# Sheet1.net
KiCad netlist of a schematic drawn in Altium Designer
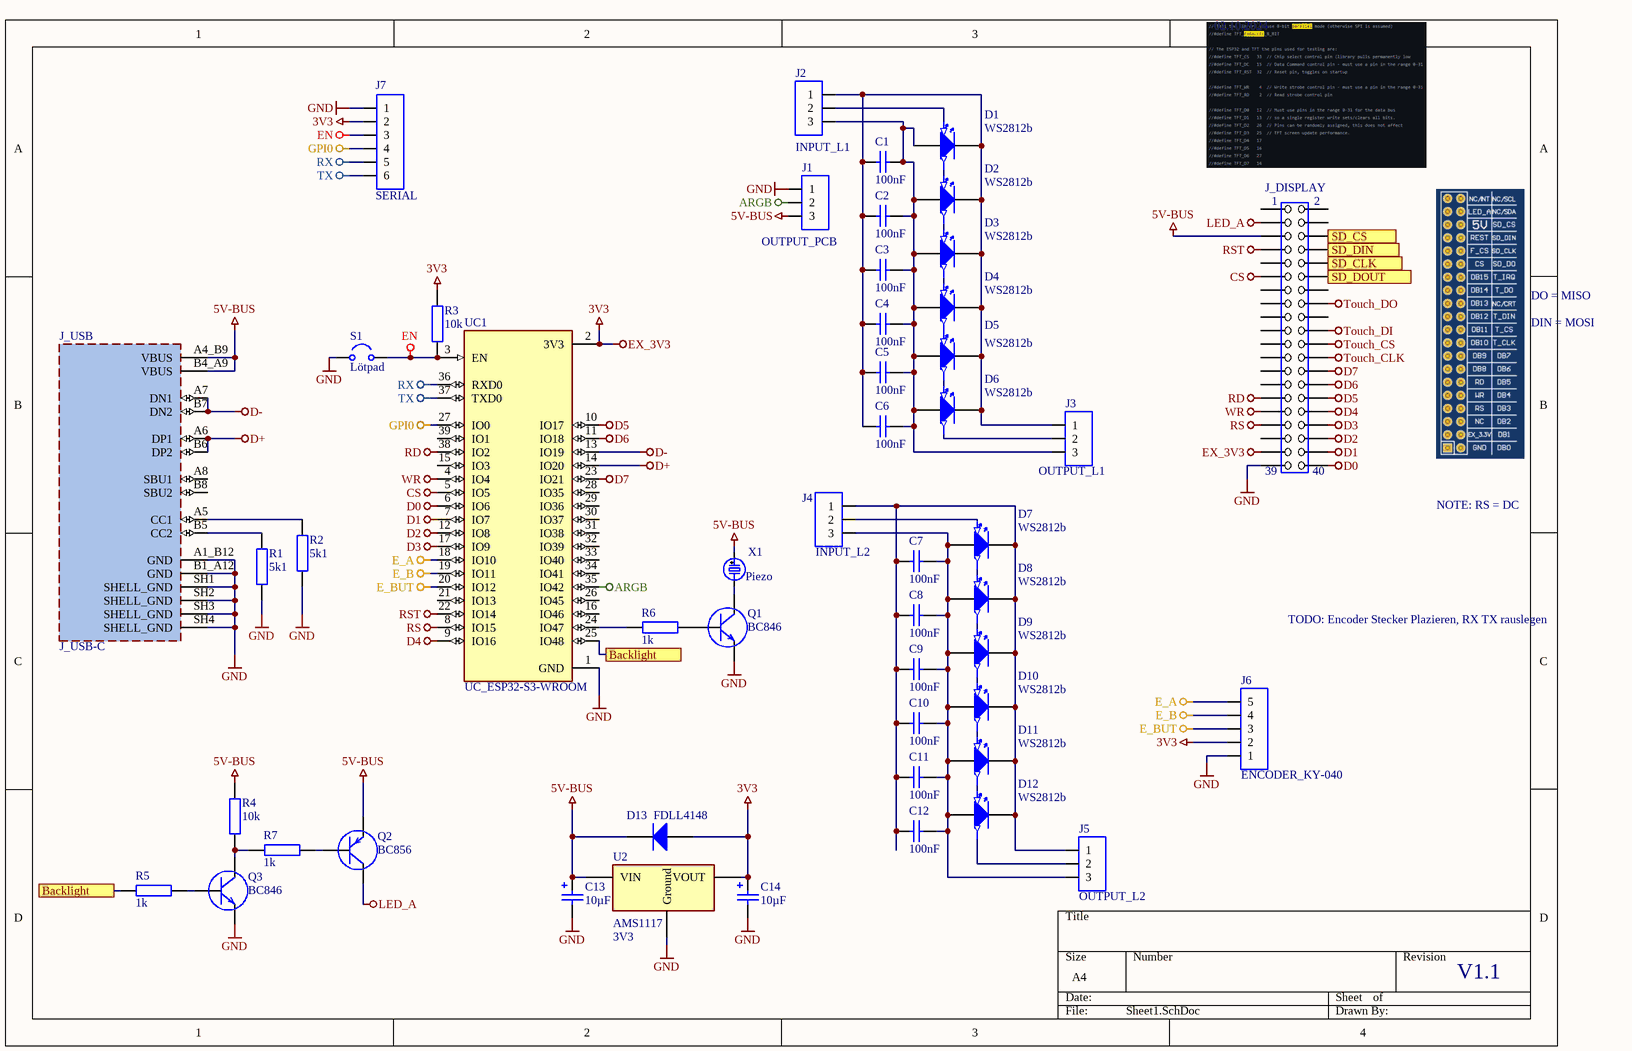
[diagram p0: Sheet1.SchDoc]

(export (version "E")
  (design (tool "Eeschema 10.0.6"))
  (components
    (comp (ref "C1")
      (value "100nF")
      (footprint "C_SMD_0603")
      (description "Kondensator SMD Universal, Keramik, Folie, usw.")
      (libsource (lib "SCHLIB-PCSB_5.1.3") (part "C_SMD_KO"))
    )
    (comp (ref "C2")
      (value "100nF")
      (footprint "C_SMD_0603")
      (description "Kondensator SMD Universal, Keramik, Folie, usw.")
      (libsource (lib "SCHLIB-PCSB_5.1.3") (part "C_SMD_KO"))
    )
    (comp (ref "C3")
      (value "100nF")
      (footprint "C_SMD_0603")
      (description "Kondensator SMD Universal, Keramik, Folie, usw.")
      (libsource (lib "SCHLIB-PCSB_5.1.3") (part "C_SMD_KO"))
    )
    (comp (ref "C4")
      (value "100nF")
      (footprint "C_SMD_0603")
      (description "Kondensator SMD Universal, Keramik, Folie, usw.")
      (libsource (lib "SCHLIB-PCSB_5.1.3") (part "C_SMD_KO"))
    )
    (comp (ref "C5")
      (value "100nF")
      (footprint "C_SMD_0603")
      (description "Kondensator SMD Universal, Keramik, Folie, usw.")
      (libsource (lib "SCHLIB-PCSB_5.1.3") (part "C_SMD_KO"))
    )
    (comp (ref "C6")
      (value "100nF")
      (footprint "C_SMD_0603")
      (description "Kondensator SMD Universal, Keramik, Folie, usw.")
      (libsource (lib "SCHLIB-PCSB_5.1.3") (part "C_SMD_KO"))
    )
    (comp (ref "C7")
      (value "100nF")
      (footprint "C_SMD_0603")
      (description "Kondensator SMD Universal, Keramik, Folie, usw.")
      (libsource (lib "SCHLIB-PCSB_5.1.3") (part "C_SMD_KO"))
    )
    (comp (ref "C8")
      (value "100nF")
      (footprint "C_SMD_0603")
      (description "Kondensator SMD Universal, Keramik, Folie, usw.")
      (libsource (lib "SCHLIB-PCSB_5.1.3") (part "C_SMD_KO"))
    )
    (comp (ref "C9")
      (value "100nF")
      (footprint "C_SMD_0603")
      (description "Kondensator SMD Universal, Keramik, Folie, usw.")
      (libsource (lib "SCHLIB-PCSB_5.1.3") (part "C_SMD_KO"))
    )
    (comp (ref "C10")
      (value "100nF")
      (footprint "C_SMD_0603")
      (description "Kondensator SMD Universal, Keramik, Folie, usw.")
      (libsource (lib "SCHLIB-PCSB_5.1.3") (part "C_SMD_KO"))
    )
    (comp (ref "C11")
      (value "100nF")
      (footprint "C_SMD_0603")
      (description "Kondensator SMD Universal, Keramik, Folie, usw.")
      (libsource (lib "SCHLIB-PCSB_5.1.3") (part "C_SMD_KO"))
    )
    (comp (ref "C12")
      (value "100nF")
      (footprint "C_SMD_0603")
      (description "Kondensator SMD Universal, Keramik, Folie, usw.")
      (libsource (lib "SCHLIB-PCSB_5.1.3") (part "C_SMD_KO"))
    )
    (comp (ref "C13")
      (value "10µF")
      (footprint "C_SMD_B-Typ")
      (description "SMD Elektrolytkondensator")
      (libsource (lib "SCHLIB-PCSB_5.1.3") (part "C_SMD_ELK"))
    )
    (comp (ref "C14")
      (value "10µF")
      (footprint "C_SMD_B-Typ")
      (description "SMD Elektrolytkondensator")
      (libsource (lib "SCHLIB-PCSB_5.1.3") (part "C_SMD_ELK"))
    )
    (comp (ref "D1")
      (value "WS2812b")
      (footprint "D_SMD_LED-ARGB")
      (description "Diode SMD ARGB")
      (libsource (lib "SCHLIB-PCSB_5.1.3") (part "D_SMD_LED-ARGB"))
    )
    (comp (ref "D2")
      (value "WS2812b")
      (footprint "D_SMD_LED-ARGB")
      (description "Diode SMD ARGB")
      (libsource (lib "SCHLIB-PCSB_5.1.3") (part "D_SMD_LED-ARGB"))
    )
    (comp (ref "D3")
      (value "WS2812b")
      (footprint "D_SMD_LED-ARGB")
      (description "Diode SMD ARGB")
      (libsource (lib "SCHLIB-PCSB_5.1.3") (part "D_SMD_LED-ARGB"))
    )
    (comp (ref "D4")
      (value "WS2812b")
      (footprint "D_SMD_LED-ARGB")
      (description "Diode SMD ARGB")
      (libsource (lib "SCHLIB-PCSB_5.1.3") (part "D_SMD_LED-ARGB"))
    )
    (comp (ref "D5")
      (value "WS2812b")
      (footprint "D_SMD_LED-ARGB")
      (description "Diode SMD ARGB")
      (libsource (lib "SCHLIB-PCSB_5.1.3") (part "D_SMD_LED-ARGB"))
    )
    (comp (ref "D6")
      (value "WS2812b")
      (footprint "D_SMD_LED-ARGB")
      (description "Diode SMD ARGB")
      (libsource (lib "SCHLIB-PCSB_5.1.3") (part "D_SMD_LED-ARGB"))
    )
    (comp (ref "D7")
      (value "WS2812b")
      (footprint "D_SMD_LED-ARGB")
      (description "Diode SMD ARGB")
      (libsource (lib "SCHLIB-PCSB_5.1.3") (part "D_SMD_LED-ARGB"))
    )
    (comp (ref "D8")
      (value "WS2812b")
      (footprint "D_SMD_LED-ARGB")
      (description "Diode SMD ARGB")
      (libsource (lib "SCHLIB-PCSB_5.1.3") (part "D_SMD_LED-ARGB"))
    )
    (comp (ref "D9")
      (value "WS2812b")
      (footprint "D_SMD_LED-ARGB")
      (description "Diode SMD ARGB")
      (libsource (lib "SCHLIB-PCSB_5.1.3") (part "D_SMD_LED-ARGB"))
    )
    (comp (ref "D10")
      (value "WS2812b")
      (footprint "D_SMD_LED-ARGB")
      (description "Diode SMD ARGB")
      (libsource (lib "SCHLIB-PCSB_5.1.3") (part "D_SMD_LED-ARGB"))
    )
    (comp (ref "D11")
      (value "WS2812b")
      (footprint "D_SMD_LED-ARGB")
      (description "Diode SMD ARGB")
      (libsource (lib "SCHLIB-PCSB_5.1.3") (part "D_SMD_LED-ARGB"))
    )
    (comp (ref "D12")
      (value "WS2812b")
      (footprint "D_SMD_LED-ARGB")
      (description "Diode SMD ARGB")
      (libsource (lib "SCHLIB-PCSB_5.1.3") (part "D_SMD_LED-ARGB"))
    )
    (comp (ref "D13")
      (value "FDLL4148")
      (footprint "SOD-80-2")
      (description "Diode SMD Silizium")
      (libsource (lib "SCHLIB-PCSB_5.1.3") (part "D_SMD_Silizium"))
    )
    (comp (ref "J1")
      (value "OUTPUT_PCB")
      (footprint "Sip-3")
      (description "Stecker")
      (libsource (lib "SCHLIB-PCSB_5.1.3") (part "J_THT_CON3"))
    )
    (comp (ref "J2")
      (value "INPUT_L1")
      (footprint "Sip-3")
      (description "Stecker")
      (libsource (lib "") (part "J_THT_CON3_1"))
    )
    (comp (ref "J3")
      (value "OUTPUT_L1")
      (footprint "Sip-3")
      (description "Stecker")
      (libsource (lib "SCHLIB-PCSB_5.1.3") (part "J_THT_CON3"))
    )
    (comp (ref "J4")
      (value "INPUT_L2")
      (footprint "Sip-3")
      (description "Stecker")
      (libsource (lib "") (part "J_THT_CON3_1"))
    )
    (comp (ref "J5")
      (value "OUTPUT_L2")
      (footprint "Sip-3")
      (description "Stecker")
      (libsource (lib "SCHLIB-PCSB_5.1.3") (part "J_THT_CON3"))
    )
    (comp (ref "J6")
      (value "ENCODER_KY-040")
      (footprint "SIP-5")
      (description "Stecker")
      (libsource (lib "SCHLIB-PCSB_5.1.3") (part "J_THT_CON5"))
    )
    (comp (ref "J7")
      (value "SERIAL")
      (footprint "SIP-6")
      (description "Stecker")
      (libsource (lib "SCHLIB-PCSB_5.1.3") (part "J_THT_CON6"))
    )
    (comp (ref "J_DISPLAY")
      (value "DISPLAY")
      (footprint "J_2x20")
      (description "IDC-Con 2x20")
      (libsource (lib "SCHLIB-PCSB_5.1.3") (part "J_THT_IDC 2x20"))
    )
    (comp (ref "J_USB")
      (value "J_USB-C")
      (footprint "GCT_USB4105-GF-A")
      (description "USB4105-GF-")
      (fields (field (name "MF") "{'manufacturer': u'GCT'}") (field (name "MP") "USB4105-GF-A"))
      (libsource (lib "SCHLIB-PCSB_5.1.3") (part "J_USB-C"))
    )
    (comp (ref "Q1")
      (value "BC846")
      (footprint "SOT-23-3_BC846")
      (description "NPN Transistor")
      (libsource (lib "SCHLIB-PCSB_5.1.3") (part "Q_SMD_NPN"))
    )
    (comp (ref "Q2")
      (value "BC856")
      (footprint "SOT-23-3_BC856")
      (description "PNP Transistor")
      (libsource (lib "SCHLIB-PCSB_5.1.3") (part "Q_SMD_PNP"))
    )
    (comp (ref "Q3")
      (value "BC846")
      (footprint "SOT-23-3_BC846")
      (description "NPN Transistor")
      (libsource (lib "SCHLIB-PCSB_5.1.3") (part "Q_SMD_NPN"))
    )
    (comp (ref "R1")
      (value "5k1")
      (footprint "R_SMD_0805")
      (description "Widerstand SMD")
      (libsource (lib "SCHLIB-PCSB_5.1.3") (part "R_SMD_Widerstand"))
    )
    (comp (ref "R2")
      (value "5k1")
      (footprint "R_SMD_0805")
      (description "Widerstand SMD")
      (libsource (lib "SCHLIB-PCSB_5.1.3") (part "R_SMD_Widerstand"))
    )
    (comp (ref "R3")
      (value "10k")
      (footprint "R_SMD_0805")
      (description "Widerstand SMD")
      (libsource (lib "SCHLIB-PCSB_5.1.3") (part "R_SMD_Widerstand"))
    )
    (comp (ref "R4")
      (value "10k")
      (footprint "R_SMD_0805")
      (description "Widerstand SMD")
      (libsource (lib "SCHLIB-PCSB_5.1.3") (part "R_SMD_Widerstand"))
    )
    (comp (ref "R5")
      (value "1k")
      (footprint "R_SMD_0805")
      (description "Widerstand SMD")
      (libsource (lib "SCHLIB-PCSB_5.1.3") (part "R_SMD_Widerstand"))
    )
    (comp (ref "R6")
      (value "1k")
      (footprint "R_SMD_0805")
      (description "Widerstand SMD")
      (libsource (lib "SCHLIB-PCSB_5.1.3") (part "R_SMD_Widerstand"))
    )
    (comp (ref "R7")
      (value "1k")
      (footprint "R_SMD_0805")
      (description "Widerstand SMD")
      (libsource (lib "SCHLIB-PCSB_5.1.3") (part "R_SMD_Widerstand"))
    )
    (comp (ref "S1")
      (value "Lötpad")
      (footprint "S_SMD_Pad-NC")
      (description "Lötverbinder")
      (libsource (lib "SCHLIB-PCSB_5.1.3") (part "S_SMD_Jumper"))
    )
    (comp (ref "U2")
      (value "AMS1117")
      (footprint "U_SMD_AMS1117")
      (description "Linearwandler")
      (fields
        (field (name "MANUFACTURER PART NUMBER") "AMS1117-3.3")
        (field (name "OCTOPART") "https://octopart.com/ams1117-3.3-advanced+monolithic+systems-25899300")
      )
      (libsource (lib "SCHLIB-PCSB_5.1.3") (part "U_SMD_AMS1117"))
    )
    (comp (ref "UC1")
      (value "UC_ESP32-S3-WROOM")
      (footprint "XCVR_ESP32S3WROOM1N8R8")
      (description "Bluetooth, WiFi 802.11b/g/n, Bluetooth v5.0 Transceiver Module 2.4GHz PCB Trace Surface Mount")
      (fields (field (name "MF") "Espressif Systems") (field (name "MP") "ESP32-S3-WROOM-1-N8R8"))
      (libsource (lib "SCHLIB-PCSB_5.1.3") (part "UC_ESP32-S3-WROOM"))
    )
    (comp (ref "X1")
      (value "Piezo")
      (footprint "X_THT_PIEZZO")
      (description "Piezobuzzer")
      (libsource (lib "SCHLIB-PCSB_5.1.3") (part "X_THT_Piezo"))
    )
  )
  (nets
    (net (code "1") (name "/Backlight") (class "Default")
      (node (ref "R5") (pin "2") (pintype "passive"))
      (node (ref "UC1") (pin "25") (pinfunction "IO48_25") (pintype "bidirectional"))
    )
    (net (code "2") (name "/SD_CLK") (class "Default")
      (node (ref "J_DISPLAY") (pin "10") (pintype "passive"))
    )
    (net (code "3") (name "/SD_CS") (class "Default") (node (ref "J_DISPLAY") (pin "6") (pintype "passive")))
    (net (code "4") (name "/SD_DIN") (class "Default") (node (ref "J_DISPLAY") (pin "8") (pintype "passive")))
    (net (code "5") (name "/SD_DOUT") (class "Default")
      (node (ref "J_DISPLAY") (pin "12") (pintype "passive"))
    )
    (net (code "6") (name "3V3") (class "Default")
      (node (ref "C14") (pin "1") (pinfunction "1_1") (pintype "passive"))
      (node (ref "D13") (pin "1") (pinfunction "A_1") (pintype "passive"))
      (node (ref "J6") (pin "2") (pinfunction "2_2") (pintype "passive"))
      (node (ref "J7") (pin "2") (pinfunction "2_2") (pintype "passive"))
      (node (ref "J_DISPLAY") (pin "37") (pintype "passive"))
      (node (ref "R3") (pin "2") (pintype "passive"))
      (node (ref "U2") (pin "2") (pinfunction "VOUT_2") (pintype "passive"))
      (node (ref "UC1") (pin "2") (pinfunction "3V3_2") (pintype "power_in"))
    )
    (net (code "7") (name "5V-BUS") (class "Default")
      (node (ref "C13") (pin "1") (pinfunction "1_1") (pintype "passive"))
      (node (ref "D13") (pin "2") (pinfunction "K_2") (pintype "passive"))
      (node (ref "J1") (pin "3") (pinfunction "3_3") (pintype "passive"))
      (node (ref "J_DISPLAY") (pin "5") (pintype "passive"))
      (node (ref "J_USB") (pin "A4_B9") (pinfunction "VBUS_A4_B9") (pintype "power_in"))
      (node (ref "J_USB") (pin "B4_A9") (pinfunction "VBUS_B4_A9") (pintype "power_in"))
      (node (ref "Q2") (pin "E") (pinfunction "E_E") (pintype "passive"))
      (node (ref "R4") (pin "2") (pintype "passive"))
      (node (ref "U2") (pin "3") (pinfunction "VIN_3") (pintype "power_in"))
      (node (ref "X1") (pin "1") (pinfunction "1_1") (pintype "passive"))
    )
    (net (code "8") (name "ARGB") (class "Default")
      (node (ref "J1") (pin "2") (pinfunction "2_2") (pintype "passive"))
      (node (ref "UC1") (pin "35") (pinfunction "IO42_35") (pintype "bidirectional"))
    )
    (net (code "9") (name "CS") (class "Default")
      (node (ref "J_DISPLAY") (pin "11") (pintype "passive"))
      (node (ref "UC1") (pin "5") (pinfunction "IO5_5") (pintype "bidirectional"))
    )
    (net (code "10") (name "D+") (class "Default")
      (node (ref "J_USB") (pin "A6") (pinfunction "DP1_A6") (pintype "bidirectional"))
      (node (ref "J_USB") (pin "B6") (pinfunction "DP2_B6") (pintype "bidirectional"))
      (node (ref "UC1") (pin "14") (pinfunction "IO20_14") (pintype "bidirectional"))
    )
    (net (code "11") (name "D-") (class "Default")
      (node (ref "J_USB") (pin "A7") (pinfunction "DN1_A7") (pintype "bidirectional"))
      (node (ref "J_USB") (pin "B7") (pinfunction "DN2_B7") (pintype "bidirectional"))
      (node (ref "UC1") (pin "13") (pinfunction "IO19_13") (pintype "bidirectional"))
    )
    (net (code "12") (name "D0") (class "Default")
      (node (ref "J_DISPLAY") (pin "40") (pintype "passive"))
      (node (ref "UC1") (pin "6") (pinfunction "IO6_6") (pintype "bidirectional"))
    )
    (net (code "13") (name "D1") (class "Default")
      (node (ref "J_DISPLAY") (pin "38") (pintype "passive"))
      (node (ref "UC1") (pin "7") (pinfunction "IO7_7") (pintype "bidirectional"))
    )
    (net (code "14") (name "D2") (class "Default")
      (node (ref "J_DISPLAY") (pin "36") (pintype "passive"))
      (node (ref "UC1") (pin "12") (pinfunction "IO8_12") (pintype "bidirectional"))
    )
    (net (code "15") (name "D3") (class "Default")
      (node (ref "J_DISPLAY") (pin "34") (pintype "passive"))
      (node (ref "UC1") (pin "17") (pinfunction "IO9_17") (pintype "bidirectional"))
    )
    (net (code "16") (name "D4") (class "Default")
      (node (ref "J_DISPLAY") (pin "32") (pintype "passive"))
      (node (ref "UC1") (pin "9") (pinfunction "IO16_9") (pintype "bidirectional"))
    )
    (net (code "17") (name "D5") (class "Default")
      (node (ref "J_DISPLAY") (pin "30") (pintype "passive"))
      (node (ref "UC1") (pin "10") (pinfunction "IO17_10") (pintype "bidirectional"))
    )
    (net (code "18") (name "D6") (class "Default")
      (node (ref "J_DISPLAY") (pin "28") (pintype "passive"))
      (node (ref "UC1") (pin "11") (pinfunction "IO18_11") (pintype "bidirectional"))
    )
    (net (code "19") (name "D7") (class "Default")
      (node (ref "J_DISPLAY") (pin "26") (pintype "passive"))
      (node (ref "UC1") (pin "23") (pinfunction "IO21_23") (pintype "bidirectional"))
    )
    (net (code "20") (name "EN") (class "Default")
      (node (ref "J7") (pin "3") (pinfunction "3_3") (pintype "passive"))
      (node (ref "R3") (pin "1") (pintype "passive"))
      (node (ref "S1") (pin "2") (pinfunction "1_2") (pintype "passive"))
      (node (ref "UC1") (pin "3") (pinfunction "EN_3") (pintype "input"))
    )
    (net (code "21") (name "E_A") (class "Default")
      (node (ref "J6") (pin "5") (pinfunction "5_5") (pintype "passive"))
      (node (ref "UC1") (pin "18") (pinfunction "IO10_18") (pintype "bidirectional"))
    )
    (net (code "22") (name "E_B") (class "Default")
      (node (ref "J6") (pin "4") (pinfunction "4_4") (pintype "passive"))
      (node (ref "UC1") (pin "19") (pinfunction "IO11_19") (pintype "bidirectional"))
    )
    (net (code "23") (name "E_BUT") (class "Default")
      (node (ref "J6") (pin "3") (pinfunction "3_3") (pintype "passive"))
      (node (ref "UC1") (pin "20") (pinfunction "IO12_20") (pintype "bidirectional"))
    )
    (net (code "24") (name "GND") (class "Default")
      (node (ref "C13") (pin "2") (pinfunction "2_2") (pintype "passive"))
      (node (ref "C14") (pin "2") (pinfunction "2_2") (pintype "passive"))
      (node (ref "J1") (pin "1") (pinfunction "1_1") (pintype "passive"))
      (node (ref "J6") (pin "1") (pinfunction "1_1") (pintype "passive"))
      (node (ref "J7") (pin "1") (pinfunction "1_1") (pintype "passive"))
      (node (ref "J_DISPLAY") (pin "39") (pintype "passive"))
      (node (ref "J_USB") (pin "A1_B12") (pinfunction "GND_A1_B12") (pintype "power_in"))
      (node (ref "J_USB") (pin "B1_A12") (pinfunction "GND_B1_A12") (pintype "power_in"))
      (node (ref "J_USB") (pin "SH1") (pinfunction "SHELL_GND_SH1") (pintype "power_in"))
      (node (ref "J_USB") (pin "SH2") (pinfunction "SHELL_GND_SH2") (pintype "power_in"))
      (node (ref "J_USB") (pin "SH3") (pinfunction "SHELL_GND_SH3") (pintype "power_in"))
      (node (ref "J_USB") (pin "SH4") (pinfunction "SHELL_GND_SH4") (pintype "power_in"))
      (node (ref "Q1") (pin "E") (pinfunction "E_E") (pintype "passive"))
      (node (ref "Q3") (pin "E") (pinfunction "E_E") (pintype "passive"))
      (node (ref "R1") (pin "1") (pintype "passive"))
      (node (ref "R2") (pin "1") (pintype "passive"))
      (node (ref "S1") (pin "1") (pinfunction "0_1") (pintype "passive"))
      (node (ref "U2") (pin "1") (pinfunction "Ground_1") (pintype "power_in"))
      (node (ref "UC1") (pin "1") (pinfunction "GND_1") (pintype "power_in"))
    )
    (net (code "25") (name "GPI0") (class "Default")
      (node (ref "J7") (pin "4") (pinfunction "4_4") (pintype "passive"))
      (node (ref "UC1") (pin "27") (pinfunction "IO0_27") (pintype "bidirectional"))
    )
    (net (code "26") (name "LED_A") (class "Default")
      (node (ref "J_DISPLAY") (pin "3") (pintype "passive"))
      (node (ref "Q2") (pin "C") (pinfunction "C_C") (pintype "passive"))
    )
    (net (code "27") (name "Net-(D1-DIN)") (class "Default")
      (node (ref "D1") (pin "4") (pinfunction "DIN_4") (pintype "input"))
      (node (ref "J2") (pin "2") (pinfunction "2_2") (pintype "passive"))
    )
    (net (code "28") (name "Net-(D1-DOUT)") (class "Default")
      (node (ref "D1") (pin "2") (pinfunction "DOUT_2") (pintype "output"))
      (node (ref "D2") (pin "4") (pinfunction "DIN_4") (pintype "input"))
    )
    (net (code "29") (name "Net-(D1-GND)") (class "Default")
      (node (ref "C1") (pin "1") (pintype "passive"))
      (node (ref "C2") (pin "1") (pintype "passive"))
      (node (ref "C3") (pin "1") (pintype "passive"))
      (node (ref "C4") (pin "1") (pintype "passive"))
      (node (ref "C5") (pin "1") (pintype "passive"))
      (node (ref "C6") (pin "1") (pintype "passive"))
      (node (ref "D1") (pin "3") (pinfunction "GND_3") (pintype "passive"))
      (node (ref "D2") (pin "3") (pinfunction "GND_3") (pintype "passive"))
      (node (ref "D3") (pin "3") (pinfunction "GND_3") (pintype "passive"))
      (node (ref "D4") (pin "3") (pinfunction "GND_3") (pintype "passive"))
      (node (ref "D5") (pin "3") (pinfunction "GND_3") (pintype "passive"))
      (node (ref "D6") (pin "3") (pinfunction "GND_3") (pintype "passive"))
      (node (ref "J2") (pin "1") (pinfunction "1_1") (pintype "passive"))
      (node (ref "J3") (pin "1") (pinfunction "1_1") (pintype "passive"))
    )
    (net (code "30") (name "Net-(D1-VDD)") (class "Default")
      (node (ref "C1") (pin "2") (pintype "passive"))
      (node (ref "C2") (pin "2") (pintype "passive"))
      (node (ref "C3") (pin "2") (pintype "passive"))
      (node (ref "C4") (pin "2") (pintype "passive"))
      (node (ref "C5") (pin "2") (pintype "passive"))
      (node (ref "C6") (pin "2") (pintype "passive"))
      (node (ref "D1") (pin "1") (pinfunction "VDD_1") (pintype "passive"))
      (node (ref "D2") (pin "1") (pinfunction "VDD_1") (pintype "passive"))
      (node (ref "D3") (pin "1") (pinfunction "VDD_1") (pintype "passive"))
      (node (ref "D4") (pin "1") (pinfunction "VDD_1") (pintype "passive"))
      (node (ref "D5") (pin "1") (pinfunction "VDD_1") (pintype "passive"))
      (node (ref "D6") (pin "1") (pinfunction "VDD_1") (pintype "passive"))
      (node (ref "J2") (pin "3") (pinfunction "3_3") (pintype "passive"))
      (node (ref "J3") (pin "3") (pinfunction "3_3") (pintype "passive"))
    )
    (net (code "31") (name "Net-(D2-DOUT)") (class "Default")
      (node (ref "D2") (pin "2") (pinfunction "DOUT_2") (pintype "output"))
      (node (ref "D3") (pin "4") (pinfunction "DIN_4") (pintype "input"))
    )
    (net (code "32") (name "Net-(D3-DOUT)") (class "Default")
      (node (ref "D3") (pin "2") (pinfunction "DOUT_2") (pintype "output"))
      (node (ref "D4") (pin "4") (pinfunction "DIN_4") (pintype "input"))
    )
    (net (code "33") (name "Net-(D4-DOUT)") (class "Default")
      (node (ref "D4") (pin "2") (pinfunction "DOUT_2") (pintype "output"))
      (node (ref "D5") (pin "4") (pinfunction "DIN_4") (pintype "input"))
    )
    (net (code "34") (name "Net-(D5-DOUT)") (class "Default")
      (node (ref "D5") (pin "2") (pinfunction "DOUT_2") (pintype "output"))
      (node (ref "D6") (pin "4") (pinfunction "DIN_4") (pintype "input"))
    )
    (net (code "35") (name "Net-(D6-DOUT)") (class "Default")
      (node (ref "D6") (pin "2") (pinfunction "DOUT_2") (pintype "output"))
      (node (ref "J3") (pin "2") (pinfunction "2_2") (pintype "passive"))
    )
    (net (code "36") (name "Net-(D7-DIN)") (class "Default")
      (node (ref "D7") (pin "4") (pinfunction "DIN_4") (pintype "input"))
      (node (ref "J4") (pin "2") (pinfunction "2_2") (pintype "passive"))
    )
    (net (code "37") (name "Net-(D7-DOUT)") (class "Default")
      (node (ref "D7") (pin "2") (pinfunction "DOUT_2") (pintype "output"))
      (node (ref "D8") (pin "4") (pinfunction "DIN_4") (pintype "input"))
    )
    (net (code "38") (name "Net-(D8-DOUT)") (class "Default")
      (node (ref "D8") (pin "2") (pinfunction "DOUT_2") (pintype "output"))
      (node (ref "D9") (pin "4") (pinfunction "DIN_4") (pintype "input"))
    )
    (net (code "39") (name "Net-(D10-DIN)") (class "Default")
      (node (ref "D10") (pin "4") (pinfunction "DIN_4") (pintype "input"))
      (node (ref "D9") (pin "2") (pinfunction "DOUT_2") (pintype "output"))
    )
    (net (code "40") (name "Net-(D10-DOUT)") (class "Default")
      (node (ref "D10") (pin "2") (pinfunction "DOUT_2") (pintype "output"))
      (node (ref "D11") (pin "4") (pinfunction "DIN_4") (pintype "input"))
    )
    (net (code "41") (name "Net-(D10-GND)") (class "Default")
      (node (ref "C10") (pin "1") (pintype "passive"))
      (node (ref "C11") (pin "1") (pintype "passive"))
      (node (ref "C12") (pin "1") (pintype "passive"))
      (node (ref "C7") (pin "1") (pintype "passive"))
      (node (ref "C8") (pin "1") (pintype "passive"))
      (node (ref "C9") (pin "1") (pintype "passive"))
      (node (ref "D10") (pin "3") (pinfunction "GND_3") (pintype "passive"))
      (node (ref "D11") (pin "3") (pinfunction "GND_3") (pintype "passive"))
      (node (ref "D12") (pin "3") (pinfunction "GND_3") (pintype "passive"))
      (node (ref "D7") (pin "3") (pinfunction "GND_3") (pintype "passive"))
      (node (ref "D8") (pin "3") (pinfunction "GND_3") (pintype "passive"))
      (node (ref "D9") (pin "3") (pinfunction "GND_3") (pintype "passive"))
      (node (ref "J4") (pin "1") (pinfunction "1_1") (pintype "passive"))
      (node (ref "J5") (pin "1") (pinfunction "1_1") (pintype "passive"))
    )
    (net (code "42") (name "Net-(D10-VDD)") (class "Default")
      (node (ref "C10") (pin "2") (pintype "passive"))
      (node (ref "C11") (pin "2") (pintype "passive"))
      (node (ref "C12") (pin "2") (pintype "passive"))
      (node (ref "C7") (pin "2") (pintype "passive"))
      (node (ref "C8") (pin "2") (pintype "passive"))
      (node (ref "C9") (pin "2") (pintype "passive"))
      (node (ref "D10") (pin "1") (pinfunction "VDD_1") (pintype "passive"))
      (node (ref "D11") (pin "1") (pinfunction "VDD_1") (pintype "passive"))
      (node (ref "D12") (pin "1") (pinfunction "VDD_1") (pintype "passive"))
      (node (ref "D7") (pin "1") (pinfunction "VDD_1") (pintype "passive"))
      (node (ref "D8") (pin "1") (pinfunction "VDD_1") (pintype "passive"))
      (node (ref "D9") (pin "1") (pinfunction "VDD_1") (pintype "passive"))
      (node (ref "J4") (pin "3") (pinfunction "3_3") (pintype "passive"))
      (node (ref "J5") (pin "3") (pinfunction "3_3") (pintype "passive"))
    )
    (net (code "43") (name "Net-(D11-DOUT)") (class "Default")
      (node (ref "D11") (pin "2") (pinfunction "DOUT_2") (pintype "output"))
      (node (ref "D12") (pin "4") (pinfunction "DIN_4") (pintype "input"))
    )
    (net (code "44") (name "Net-(D12-DOUT)") (class "Default")
      (node (ref "D12") (pin "2") (pinfunction "DOUT_2") (pintype "output"))
      (node (ref "J5") (pin "2") (pinfunction "2_2") (pintype "passive"))
    )
    (net (code "45") (name "Net-(J_USB-CC1)") (class "Default")
      (node (ref "J_USB") (pin "A5") (pinfunction "CC1_A5") (pintype "bidirectional"))
      (node (ref "R2") (pin "2") (pintype "passive"))
    )
    (net (code "46") (name "Net-(J_USB-CC2)") (class "Default")
      (node (ref "J_USB") (pin "B5") (pinfunction "CC2_B5") (pintype "bidirectional"))
      (node (ref "R1") (pin "2") (pintype "passive"))
    )
    (net (code "47") (name "Net-(Q1-PadB)") (class "Default")
      (node (ref "Q1") (pin "B") (pinfunction "B_B") (pintype "passive"))
      (node (ref "R6") (pin "1") (pintype "passive"))
    )
    (net (code "48") (name "Net-(Q1-PadC)") (class "Default")
      (node (ref "Q1") (pin "C") (pinfunction "C_C") (pintype "passive"))
      (node (ref "X1") (pin "2") (pinfunction "2_2") (pintype "passive"))
    )
    (net (code "49") (name "Net-(Q2-PadB)") (class "Default")
      (node (ref "Q2") (pin "B") (pinfunction "B_B") (pintype "passive"))
      (node (ref "R7") (pin "1") (pintype "passive"))
    )
    (net (code "50") (name "Net-(Q3-PadB)") (class "Default")
      (node (ref "Q3") (pin "B") (pinfunction "B_B") (pintype "passive"))
      (node (ref "R5") (pin "1") (pintype "passive"))
    )
    (net (code "51") (name "Net-(Q3-PadC)") (class "Default")
      (node (ref "Q3") (pin "C") (pinfunction "C_C") (pintype "passive"))
      (node (ref "R4") (pin "1") (pintype "passive"))
      (node (ref "R7") (pin "2") (pintype "passive"))
    )
    (net (code "52") (name "Net-(UC1-IO47)") (class "Default")
      (node (ref "R6") (pin "2") (pintype "passive"))
      (node (ref "UC1") (pin "24") (pinfunction "IO47_24") (pintype "bidirectional"))
    )
    (net (code "53") (name "RD") (class "Default")
      (node (ref "J_DISPLAY") (pin "29") (pintype "passive"))
      (node (ref "UC1") (pin "38") (pinfunction "IO2_38") (pintype "bidirectional"))
    )
    (net (code "54") (name "RS") (class "Default")
      (node (ref "J_DISPLAY") (pin "33") (pintype "passive"))
      (node (ref "UC1") (pin "8") (pinfunction "IO15_8") (pintype "bidirectional"))
    )
    (net (code "55") (name "RST") (class "Default")
      (node (ref "J_DISPLAY") (pin "7") (pintype "passive"))
      (node (ref "UC1") (pin "22") (pinfunction "IO14_22") (pintype "bidirectional"))
    )
    (net (code "56") (name "RX") (class "Default")
      (node (ref "J7") (pin "5") (pinfunction "5_5") (pintype "passive"))
      (node (ref "UC1") (pin "36") (pinfunction "RXD0_36") (pintype "bidirectional"))
    )
    (net (code "57") (name "TX") (class "Default")
      (node (ref "J7") (pin "6") (pinfunction "6_6") (pintype "passive"))
      (node (ref "UC1") (pin "37") (pinfunction "TXD0_37") (pintype "bidirectional"))
    )
    (net (code "58") (name "Touch_CLK") (class "Default")
      (node (ref "J_DISPLAY") (pin "24") (pintype "passive"))
    )
    (net (code "59") (name "Touch_CS") (class "Default")
      (node (ref "J_DISPLAY") (pin "22") (pintype "passive"))
    )
    (net (code "60") (name "Touch_DI") (class "Default")
      (node (ref "J_DISPLAY") (pin "20") (pintype "passive"))
    )
    (net (code "61") (name "Touch_DO") (class "Default")
      (node (ref "J_DISPLAY") (pin "16") (pintype "passive"))
    )
    (net (code "62") (name "WR") (class "Default")
      (node (ref "J_DISPLAY") (pin "31") (pintype "passive"))
      (node (ref "UC1") (pin "4") (pinfunction "IO4_4") (pintype "bidirectional"))
    )
    (net (code "63") (name "unconnected-(J_DISPLAY-Pad1)") (class "Default")
      (node (ref "J_DISPLAY") (pin "1") (pintype "passive"))
    )
    (net (code "64") (name "unconnected-(J_DISPLAY-Pad2)") (class "Default")
      (node (ref "J_DISPLAY") (pin "2") (pintype "passive"))
    )
    (net (code "65") (name "unconnected-(J_DISPLAY-Pad4)") (class "Default")
      (node (ref "J_DISPLAY") (pin "4") (pintype "passive"))
    )
    (net (code "66") (name "unconnected-(J_DISPLAY-Pad9)") (class "Default")
      (node (ref "J_DISPLAY") (pin "9") (pintype "passive"))
    )
    (net (code "67") (name "unconnected-(J_DISPLAY-Pad13)") (class "Default")
      (node (ref "J_DISPLAY") (pin "13") (pintype "passive"))
    )
    (net (code "68") (name "unconnected-(J_DISPLAY-Pad14)") (class "Default")
      (node (ref "J_DISPLAY") (pin "14") (pintype "passive"))
    )
    (net (code "69") (name "unconnected-(J_DISPLAY-Pad15)") (class "Default")
      (node (ref "J_DISPLAY") (pin "15") (pintype "passive"))
    )
    (net (code "70") (name "unconnected-(J_DISPLAY-Pad17)") (class "Default")
      (node (ref "J_DISPLAY") (pin "17") (pintype "passive"))
    )
    (net (code "71") (name "unconnected-(J_DISPLAY-Pad18)") (class "Default")
      (node (ref "J_DISPLAY") (pin "18") (pintype "passive"))
    )
    (net (code "72") (name "unconnected-(J_DISPLAY-Pad19)") (class "Default")
      (node (ref "J_DISPLAY") (pin "19") (pintype "passive"))
    )
    (net (code "73") (name "unconnected-(J_DISPLAY-Pad21)") (class "Default")
      (node (ref "J_DISPLAY") (pin "21") (pintype "passive"))
    )
    (net (code "74") (name "unconnected-(J_DISPLAY-Pad23)") (class "Default")
      (node (ref "J_DISPLAY") (pin "23") (pintype "passive"))
    )
    (net (code "75") (name "unconnected-(J_DISPLAY-Pad25)") (class "Default")
      (node (ref "J_DISPLAY") (pin "25") (pintype "passive"))
    )
    (net (code "76") (name "unconnected-(J_DISPLAY-Pad27)") (class "Default")
      (node (ref "J_DISPLAY") (pin "27") (pintype "passive"))
    )
    (net (code "77") (name "unconnected-(J_DISPLAY-Pad35)") (class "Default")
      (node (ref "J_DISPLAY") (pin "35") (pintype "passive"))
    )
    (net (code "78") (name "unconnected-(J_USB-SBU1-PadA8)") (class "Default")
      (node (ref "J_USB") (pin "A8") (pinfunction "SBU1_A8") (pintype "bidirectional"))
    )
    (net (code "79") (name "unconnected-(J_USB-SBU2-PadB8)") (class "Default")
      (node (ref "J_USB") (pin "B8") (pinfunction "SBU2_B8") (pintype "bidirectional"))
    )
    (net (code "80") (name "unconnected-(UC1-IO1-Pad39)") (class "Default")
      (node (ref "UC1") (pin "39") (pinfunction "IO1_39") (pintype "bidirectional"))
    )
    (net (code "81") (name "unconnected-(UC1-IO3-Pad15)") (class "Default")
      (node (ref "UC1") (pin "15") (pinfunction "IO3_15") (pintype "bidirectional"))
    )
    (net (code "82") (name "unconnected-(UC1-IO13-Pad21)") (class "Default")
      (node (ref "UC1") (pin "21") (pinfunction "IO13_21") (pintype "bidirectional"))
    )
    (net (code "83") (name "unconnected-(UC1-IO35-Pad28)") (class "Default")
      (node (ref "UC1") (pin "28") (pinfunction "IO35_28") (pintype "bidirectional"))
    )
    (net (code "84") (name "unconnected-(UC1-IO36-Pad29)") (class "Default")
      (node (ref "UC1") (pin "29") (pinfunction "IO36_29") (pintype "bidirectional"))
    )
    (net (code "85") (name "unconnected-(UC1-IO37-Pad30)") (class "Default")
      (node (ref "UC1") (pin "30") (pinfunction "IO37_30") (pintype "bidirectional"))
    )
    (net (code "86") (name "unconnected-(UC1-IO38-Pad31)") (class "Default")
      (node (ref "UC1") (pin "31") (pinfunction "IO38_31") (pintype "bidirectional"))
    )
    (net (code "87") (name "unconnected-(UC1-IO39-Pad32)") (class "Default")
      (node (ref "UC1") (pin "32") (pinfunction "IO39_32") (pintype "bidirectional"))
    )
    (net (code "88") (name "unconnected-(UC1-IO40-Pad33)") (class "Default")
      (node (ref "UC1") (pin "33") (pinfunction "IO40_33") (pintype "bidirectional"))
    )
    (net (code "89") (name "unconnected-(UC1-IO41-Pad34)") (class "Default")
      (node (ref "UC1") (pin "34") (pinfunction "IO41_34") (pintype "bidirectional"))
    )
    (net (code "90") (name "unconnected-(UC1-IO45-Pad26)") (class "Default")
      (node (ref "UC1") (pin "26") (pinfunction "IO45_26") (pintype "bidirectional"))
    )
    (net (code "91") (name "unconnected-(UC1-IO46-Pad16)") (class "Default")
      (node (ref "UC1") (pin "16") (pinfunction "IO46_16") (pintype "bidirectional"))
    )
  )
)
